# NANO33BLE.net
KiCad netlist of a schematic drawn in Altium Designer
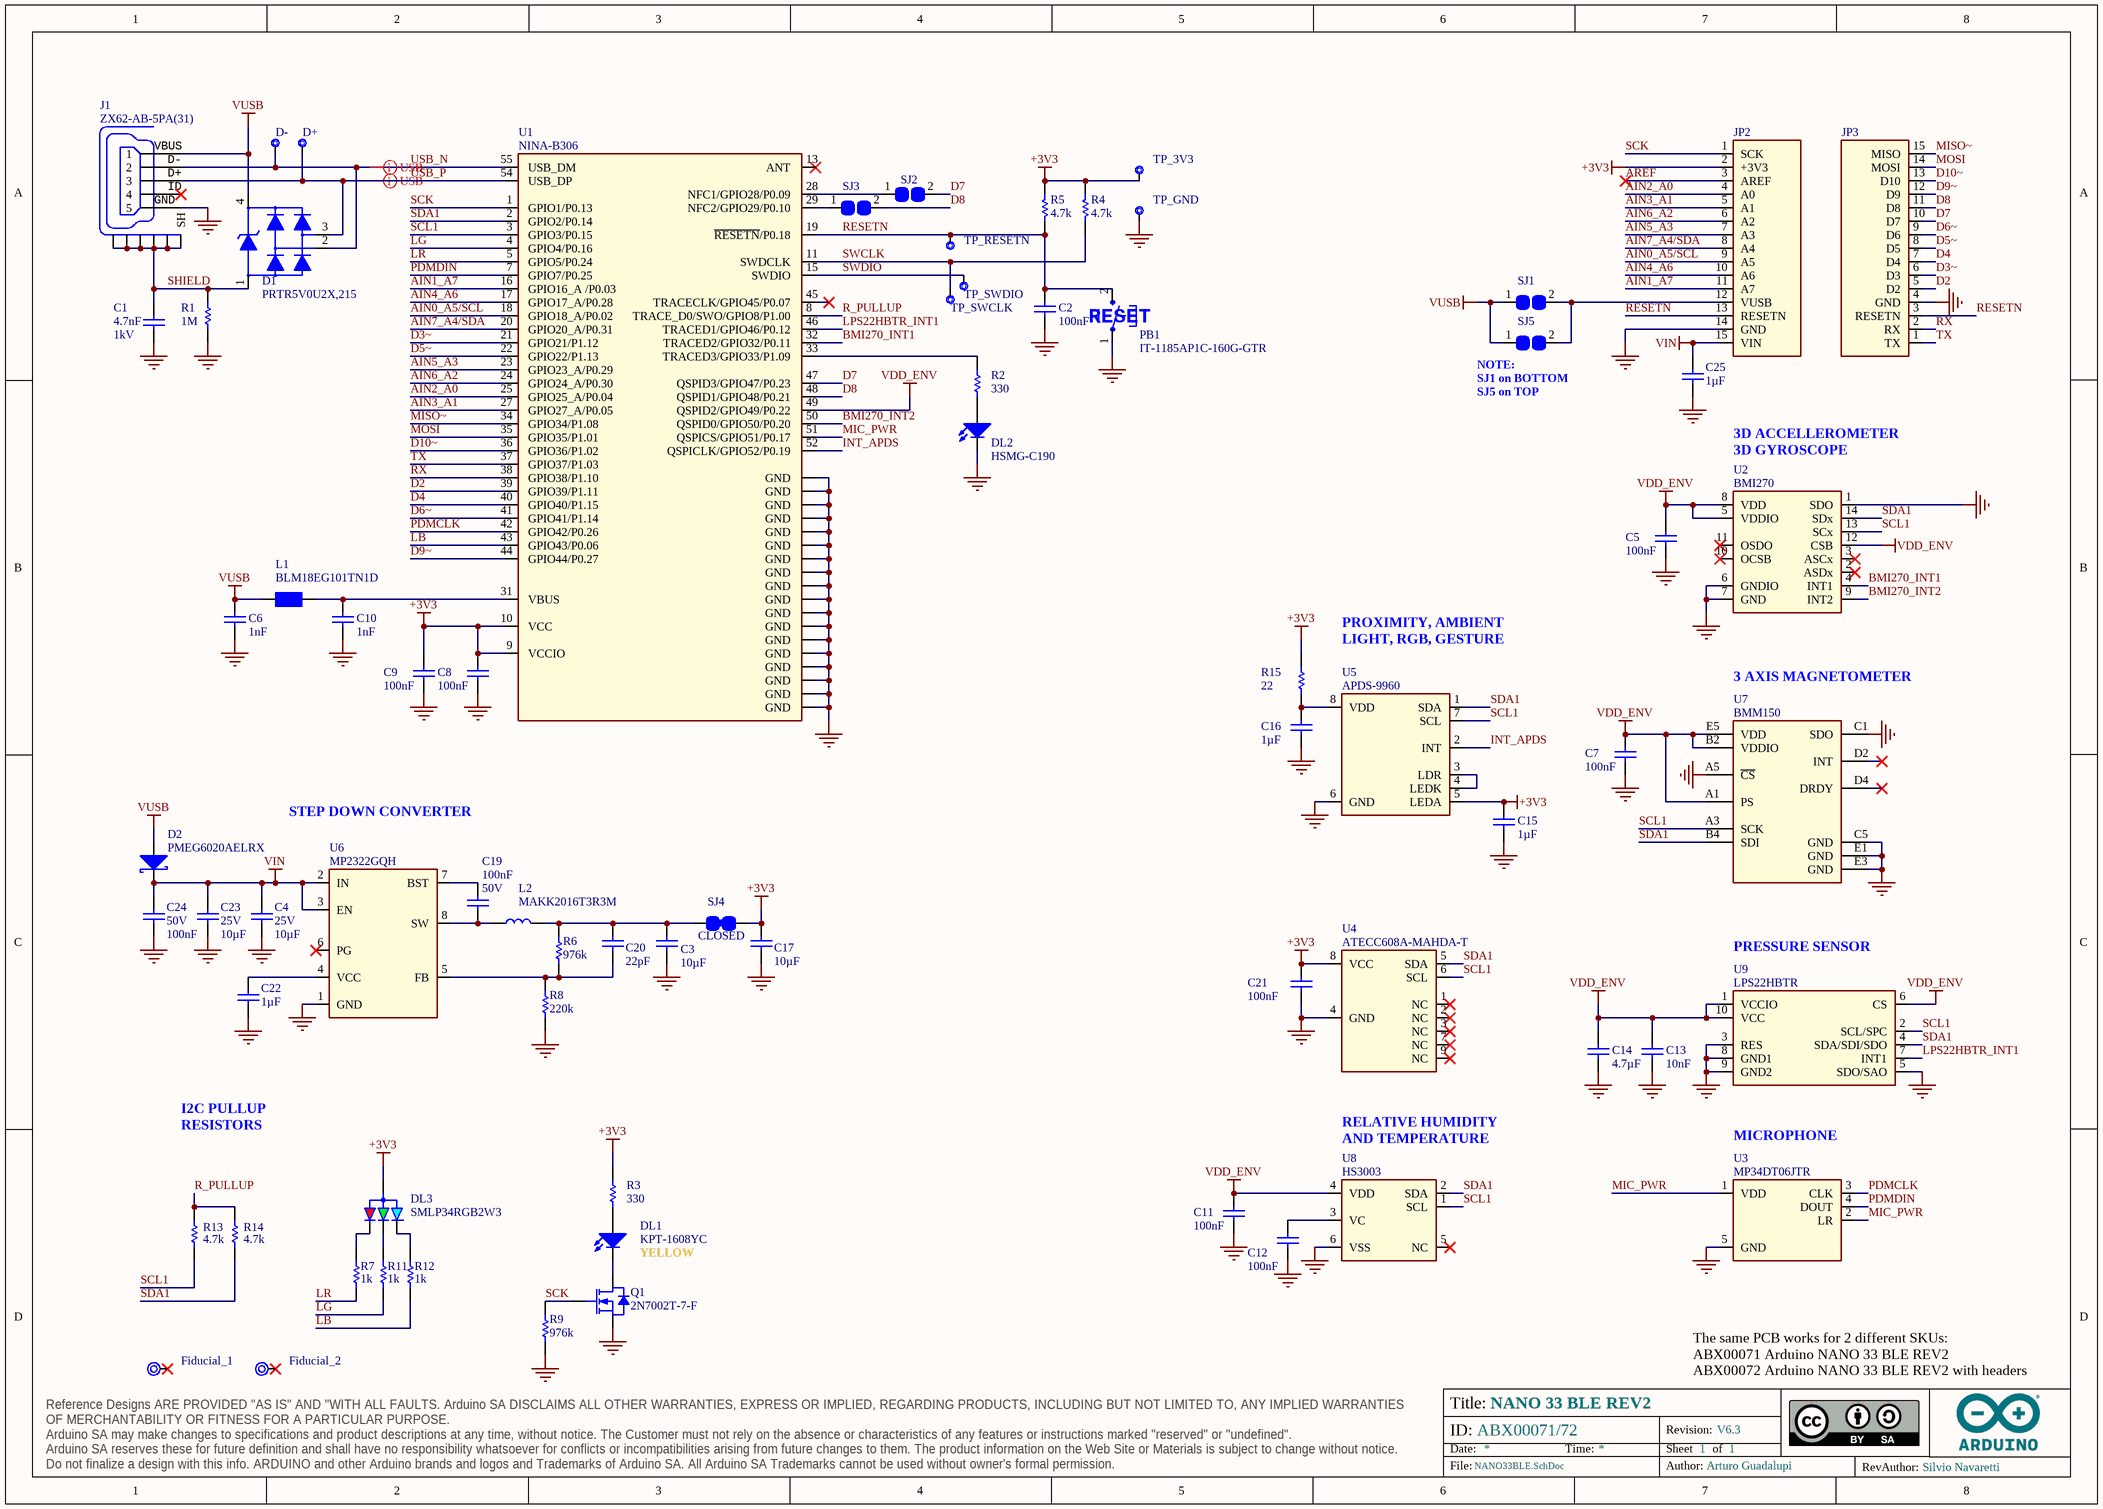
[diagram p0: NANO33BLE.SchDoc]

(export (version "E")
  (design (tool "Eeschema 10.0.6"))
  (components
    (comp (ref "C1")
      (value "4.7nF")
      (footprint "CAP-0805")
      (description "CAP CHIP 0805 4.7nF 10% 1000V X7R")
      (fields
        (field (name "MANUFACTURER") "PSA Shenzen")
        (field (name "VOLTAGE") "1kV")
        (field (name "TOLERANCE") "10%")
      )
      (libsource (lib "Clean") (part "CAP"))
    )
    (comp (ref "C2")
      (value "100nF")
      (footprint "CAP-0402")
      (description "CAP CHIP 0402 100nF 10% 50V X5R")
      (fields (field (name "MANUFACTURER") "Murata") (field (name "PART NUMBER") "GRM155R61H104KE19D"))
      (libsource (lib "Clean") (part "CAP"))
    )
    (comp (ref "C3")
      (value "10µF")
      (footprint "CAP-0603")
      (description "CAP CHIP 0603 10uF 20% 25V X5R")
      (fields (field (name "VOLTAGE") "25V") (field (name "PART NUMBER") "C1608A106M250NT"))
      (libsource (lib "Clean") (part "CAP"))
    )
    (comp (ref "C4")
      (value "10µF")
      (footprint "CAP-0603")
      (description "CAP CHIP 0603 10uF 20% 25V X5R")
      (fields
        (field (name "VOLTAGE") "25V")
        (field (name "PART NUMBER") "C1608A106M250NT")
        (field (name "TOLERANCE") "20%")
      )
      (libsource (lib "Clean") (part "CAP"))
    )
    (comp (ref "C5")
      (value "100nF")
      (footprint "CAP-0402")
      (description "CAP CHIP 0402 100nF 10% 16V X7R")
      (fields (field (name "MANUFACTURER") "Walsin") (field (name "PART NUMBER") "0402B104K160CT"))
      (libsource (lib "Clean") (part "CAP"))
    )
    (comp (ref "C6")
      (value "1nF")
      (footprint "CAP-0402")
      (description "CAP CHIP 0402 1nF 10% 50V X7R")
      (fields (field (name "MANUFACTURER") "KEMET") (field (name "PART NUMBER") "GRM155R71H102KA01D"))
      (libsource (lib "Clean") (part "CAP"))
    )
    (comp (ref "C7")
      (value "100nF")
      (footprint "CAP-0402")
      (description "CAP CHIP 0402 100nF 10% 50V X5R")
      (fields (field (name "VOLTAGE") "50V") (field (name "TOLERANCE") "10%"))
      (libsource (lib "Clean") (part "CAP"))
    )
    (comp (ref "C8")
      (value "100nF")
      (footprint "CAP-0402")
      (description "CAP CHIP 0402 100nF 10% 50V X5R")
      (fields (field (name "MANUFACTURER") "Murata") (field (name "PART NUMBER") "GRM155R61H104KE19D"))
      (libsource (lib "Clean") (part "CAP"))
    )
    (comp (ref "C9")
      (value "100nF")
      (footprint "CAP-0402")
      (description "CAP CHIP 0402 100nF 10% 50V X5R")
      (fields (field (name "MANUFACTURER") "Murata") (field (name "PART NUMBER") "GRM155R61H104KE19D"))
      (libsource (lib "Clean") (part "CAP"))
    )
    (comp (ref "C10")
      (value "1nF")
      (footprint "CAP-0402")
      (description "CAP CHIP 0402 1nF 10% 50V X7R")
      (fields (field (name "MANUFACTURER") "KEMET") (field (name "PART NUMBER") "GRM155R71H102KA01D"))
      (libsource (lib "Clean") (part "CAP"))
    )
    (comp (ref "C11")
      (value "100nF")
      (footprint "CAP-0402")
      (description "CAP CHIP 0402 100nF 10% 50V X5R")
      (fields (field (name "MANUFACTURER") "Murata") (field (name "PART NUMBER") "GRM155R61H104KE19D"))
      (libsource (lib "Clean") (part "CAP"))
    )
    (comp (ref "C12")
      (value "100nF")
      (footprint "CAP-0402")
      (description "CAP CHIP 0402 100nF 10% 50V X5R")
      (fields (field (name "MANUFACTURER") "Murata") (field (name "PART NUMBER") "GRM155R61H104KE19D"))
      (libsource (lib "Clean") (part "CAP"))
    )
    (comp (ref "C13")
      (value "10nF")
      (footprint "CAP-0402")
      (description "CAP CHIP 0402 10nF 10% 50V X7R")
      (fields (field (name "MANUFACTURER") "Hottech") (field (name "VOLTAGE") "50V"))
      (libsource (lib "Clean") (part "CAP"))
    )
    (comp (ref "C14")
      (value "4.7µF")
      (footprint "CAP-0402")
      (description "CAP CHIP 0402 4.7uF 20% 6V3 X5R")
      (fields (field (name "MANUFACTURER") "Hottech") (field (name "PART NUMBER") "C1005A475M6R3NT"))
      (libsource (lib "Clean") (part "CAP"))
    )
    (comp (ref "C15")
      (value "1µF")
      (footprint "CAP-0402")
      (description "CAP CHIP 0402 1uF 10% 10V X5R")
      (fields (field (name "MANUFACTURER") "Samsung Electro-Mechanics") (field (name "VOLTAGE") "10V"))
      (libsource (lib "Clean") (part "CAP"))
    )
    (comp (ref "C16")
      (value "1µF")
      (footprint "CAP-0402")
      (description "CAP CHIP 0402 1uF 10% 10V X5R")
      (fields (field (name "MANUFACTURER") "Samsung Electro-Mechanics") (field (name "VOLTAGE") "10V"))
      (libsource (lib "Clean") (part "CAP"))
    )
    (comp (ref "C17")
      (value "10µF")
      (footprint "CAP-0603")
      (description "CAP CHIP 0603 10uF 20% 25V X5R")
      (fields (field (name "VOLTAGE") "25V") (field (name "PART NUMBER") "C1608A106M250NT"))
      (libsource (lib "Clean") (part "CAP"))
    )
    (comp (ref "C19")
      (value "100nF")
      (footprint "CAP-0402")
      (description "CAP CHIP 0402 100nF 10% 50V X5R")
      (fields
        (field (name "VOLTAGE") "50V")
        (field (name "PART NUMBER") "GRM155R61H104KE19D")
        (field (name "MANUFACTURER") "Murata")
      )
      (libsource (lib "Clean") (part "CAP"))
    )
    (comp (ref "C20")
      (value "22pF")
      (footprint "CAP-0402")
      (description "CAP CHIP 0402 22pF 5% 50V C0G")
      (fields (field (name "TOLERANCE") "5%") (field (name "PART NUMBER") "0402N220J500CT"))
      (libsource (lib "Clean") (part "CAP"))
    )
    (comp (ref "C21")
      (value "100nF")
      (footprint "CAP-0402")
      (description "CAP CHIP 0402 100nF 10% 50V X5R")
      (fields (field (name "MANUFACTURER") "Murata") (field (name "PART NUMBER") "GRM155R61H104KE19D"))
      (libsource (lib "Clean") (part "CAP"))
    )
    (comp (ref "C22")
      (value "1µF")
      (footprint "CAP-0402")
      (description "CAP CHIP 0402 1uF 10% 10V X5R")
      (fields (field (name "TOLERANCE") "10%") (field (name "MANUFACTURER") "Samsung Electro-Mechanics"))
      (libsource (lib "Clean") (part "CAP"))
    )
    (comp (ref "C23")
      (value "10µF")
      (footprint "CAP-0603")
      (description "CAP CHIP 0603 10uF 20% 25V X5R")
      (fields
        (field (name "VOLTAGE") "25V")
        (field (name "PART NUMBER") "C1608A106M250NT")
        (field (name "TOLERANCE") "20%")
      )
      (libsource (lib "Clean") (part "CAP"))
    )
    (comp (ref "C24")
      (value "100nF")
      (footprint "CAP-0402")
      (description "CAP CHIP 0402 100nF 10% 50V X5R")
      (fields
        (field (name "MANUFACTURER") "Murata")
        (field (name "PART NUMBER") "GRM155R61H104KE19D")
        (field (name "VOLTAGE") "50V")
      )
      (libsource (lib "Clean") (part "CAP"))
    )
    (comp (ref "C25")
      (value "1µF")
      (footprint "CAP-0402")
      (description "CAP CHIP 0402 1uF 10% 10V X5R")
      (fields
        (field (name "MANUFACTURER") "Samsung Electro-Mechanics")
        (field (name "PART NUMBER") "CL05A105KP5NNNC")
      )
      (libsource (lib "Clean") (part "CAP"))
    )
    (comp (ref "D+")
      (value "CMP-018-0005-A.3")
      (footprint "TP-1.00MM")
      (description "Test point 1.00mm")
      (libsource (lib "Clean") (part "TESTPOINT"))
    )
    (comp (ref "D-")
      (value "CMP-018-0005-A.3")
      (footprint "TP-1.00MM")
      (description "Test point 1.00mm")
      (libsource (lib "Clean") (part "TESTPOINT"))
    )
    (comp (ref "D1")
      (value "PRTR5V0U2X,215")
      (footprint "SOT190P230X110-4N")
      (description "TVS ARRAY 4LIN.8kV 1pF SOT143B")
      (fields (field (name "MANUFACTURER") "Nexperia"))
      (libsource (lib "Clean") (part "PRTR5V0U2X,215"))
    )
    (comp (ref "D2")
      (value "PMEG6020AELRX")
      (footprint "SOD123-1")
      (description "DIODE SCHOTTKY SMD 2A 60V SOD123FL")
      (fields (field (name "MANUFACTURER") "Nexperia"))
      (libsource (lib "Clean") (part "PMEG6020AELRX"))
    )
    (comp (ref "DL1")
      (value "KPT-1608YC")
      (footprint "LEDC1608X80N-AK")
      (description "LED SMD 0603 GIA588   8mcd 120^")
      (fields (field (name "MANUFACTURER") "Kingbright"))
      (libsource (lib "Clean") (part "LED"))
    )
    (comp (ref "DL2")
      (value "HSMG-C190")
      (footprint "LEDC1608X80N-AK")
      (description "LED SMD 0603 GREEN/568 15mcd 120^")
      (fields (field (name "MANUFACTURER") "Broadcom"))
      (libsource (lib "Clean") (part "LED"))
    )
    (comp (ref "DL3")
      (value "SMLP34RGB2W3")
      (footprint "SMLP34RGB2W")
      (description "LED RGB DIFFUSED PICOLED SMD")
      (fields (field (name "MANUFACTURER") "ROHM Semiconductor"))
      (libsource (lib "Clean") (part "SMLP34RGB2W3"))
    )
    (comp (ref "Fiducial_1")
      (value "Fiducial mark 1mm with 2mm solder")
      (footprint "Fiducial mark 1mm with circle-Footprint-1")
      (libsource (lib "Clean") (part "Fiducial mark 1mm with circle"))
    )
    (comp (ref "Fiducial_2")
      (value "Fiducial mark 1mm with 2mm solder")
      (footprint "Fiducial mark 1mm with circle-Footprint-1")
      (libsource (lib "Clean") (part "Fiducial mark 1mm with circle"))
    )
    (comp (ref "J1")
      (value "ZX62-AB-5PA(31)")
      (footprint "ZX62-AB-5PA")
      (description "CONN USB MICRO F/90^ SMD TipoAB 5x1")
      (fields (field (name "MANUFACTURER") "Hirose"))
      (libsource (lib "Clean") (part "ZX62-AB-5PA(31)"))
    )
    (comp (ref "JP2")
      (value "PINHD-1X15-NANO-ANALOG-CASTELLATED")
      (footprint "PINHD-1X14_5VF")
      (description "CONN THD SOCKET F/1/D 15V JANALOG NANO-TYPE CASTELLATED")
      (libsource (lib "Clean") (part "PINHD-1X15-NANO-ANALOG-CASTELLATED"))
    )
    (comp (ref "JP3")
      (value "PINHD-1X15-NANO-DIGITAL-CASTELLATED")
      (footprint "PINHD-1X14_5VF")
      (description "CONN THD SOCKET F/1/D 15V JDIGITAL NANO-TYPE CASTELLATED")
      (libsource (lib "Clean") (part "PINHD-1X15-NANO-DIGITAL"))
    )
    (comp (ref "L1")
      (value "BLM18EG101TN1D")
      (footprint "L-0603")
      (description "FERRITE SMD 0603 45mOHM 2A")
      (fields
        (field (name "MANUFACTURER") "Murata")
        (field (name "PART NUMBER") "BLM18EG101TN1D")
        (field (name "TOLERANCE") "25%")
      )
      (libsource (lib "Clean") (part "Ferrite"))
    )
    (comp (ref "L2")
      (value "MAKK2016T3R3M")
      (footprint "MAKK2016T3R3M-Footprint-1")
      (description "IND CHIP 0806 3.3 uH 20% 1.2A")
      (fields (field (name "TOLERANCE") "20%") (field (name "MANUFACTURER") "Taiyo Yuden"))
      (libsource (lib "Clean") (part "Inductor"))
    )
    (comp (ref "PB1")
      (value "IT-1185AP1C-160G-GTR")
      (footprint "C&K_PTS820_NO_HOLES-1")
      (description "PUSHBUTTON WHITE NO ANCHORS")
      (fields (field (name "MANUFACTURER") "Switronic"))
      (libsource (lib "Clean") (part "PTS820"))
    )
    (comp (ref "Q1")
      (value "2N7002T-7-F")
      (footprint "SOT523")
      (description "MOSFET N-CH 60V 115mA SOT523")
      (fields (field (name "MANUFACTURER") "Diodes Inc."))
      (libsource (lib "Clean") (part "NMOS"))
    )
    (comp (ref "R1")
      (value "1M")
      (footprint "RES-0402")
      (description "RES CHIP 0402 1M 1% 1/16W")
      (fields (field (name "MANUFACTURER") "Vishay") (field (name "POWER") "62.5mW"))
      (libsource (lib "Clean") (part "RES"))
    )
    (comp (ref "R2")
      (value "330")
      (footprint "RES-0402")
      (description "RES CHIP 0402 330R 5% 1/16W")
      (fields (field (name "MANUFACTURER") "Vishay") (field (name "POWER") "62.5mW"))
      (libsource (lib "Clean") (part "RES"))
    )
    (comp (ref "R3")
      (value "330")
      (footprint "RES-0402")
      (description "RES CHIP 0402 330R 5% 1/16W")
      (fields (field (name "MANUFACTURER") "Vishay") (field (name "POWER") "62.5mW"))
      (libsource (lib "Clean") (part "RES"))
    )
    (comp (ref "R4")
      (value "4.7k")
      (footprint "RES-0402")
      (description "RES CHIP 0402 4k7 1% 1/16W")
      (fields (field (name "MANUFACTURER") "YAGEO") (field (name "PART NUMBER") "RC0402FR-074K7L"))
      (libsource (lib "Clean") (part "RES"))
    )
    (comp (ref "R5")
      (value "4.7k")
      (footprint "RES-0402")
      (description "RES CHIP 0402 4k7 1% 1/16W")
      (fields (field (name "MANUFACTURER") "YAGEO") (field (name "PART NUMBER") "RC0402FR-074K7L"))
      (libsource (lib "Clean") (part "RES"))
    )
    (comp (ref "R6")
      (value "976k")
      (footprint "RES-0402")
      (description "RES CHIP 0402 976k 1% 1/16W")
      (fields (field (name "TOLERANCE") "1%") (field (name "POWER") "62.5mW"))
      (libsource (lib "Clean") (part "RES"))
    )
    (comp (ref "R7")
      (value "1k")
      (footprint "RES-0402")
      (description "RES CHIP 0402 1k 1% 1/16W")
      (fields (field (name "MANUFACTURER") "Vishay") (field (name "POWER") "62.5mW"))
      (libsource (lib "Clean") (part "RES"))
    )
    (comp (ref "R8")
      (value "220k")
      (footprint "RES-0402")
      (description "RES CHIP 0402 220k 1% 1/16W")
      (fields (field (name "MANUFACTURER") "Vishay") (field (name "PART NUMBER") "CRCW0402220KFKED"))
      (libsource (lib "Clean") (part "RES"))
    )
    (comp (ref "R9")
      (value "976k")
      (footprint "RES-0402")
      (description "RES CHIP 0402 976k 1% 1/16W")
      (fields (field (name "TOLERANCE") "1%") (field (name "POWER") "62.5mW"))
      (libsource (lib "Clean") (part "RES"))
    )
    (comp (ref "R11")
      (value "1k")
      (footprint "RES-0402")
      (description "RES CHIP 0402 1k 1% 1/16W")
      (fields (field (name "MANUFACTURER") "Vishay") (field (name "POWER") "62.5mW"))
      (libsource (lib "Clean") (part "RES"))
    )
    (comp (ref "R12")
      (value "1k")
      (footprint "RES-0402")
      (description "RES CHIP 0402 1k 1% 1/16W")
      (fields (field (name "MANUFACTURER") "Vishay") (field (name "POWER") "62.5mW"))
      (libsource (lib "Clean") (part "RES"))
    )
    (comp (ref "R13")
      (value "4.7k")
      (footprint "RES-0402")
      (description "RES CHIP 0402 4k7 1% 1/16W")
      (fields (field (name "MANUFACTURER") "YAGEO") (field (name "PART NUMBER") "RC0402FR-074K7L"))
      (libsource (lib "Clean") (part "RES"))
    )
    (comp (ref "R14")
      (value "4.7k")
      (footprint "RES-0402")
      (description "RES CHIP 0402 4k7 1% 1/16W")
      (fields (field (name "MANUFACTURER") "YAGEO") (field (name "PART NUMBER") "RC0402FR-074K7L"))
      (libsource (lib "Clean") (part "RES"))
    )
    (comp (ref "R15")
      (value "22")
      (footprint "RES-0402")
      (description "RES CHIP 0402 22R 1% 1/16W")
      (fields (field (name "MANUFACTURER") "YAGEO") (field (name "TOLERANCE") "1%"))
      (libsource (lib "Clean") (part "RES"))
    )
    (comp (ref "SJ1")
      (value "SMD solder JUMPER 0805")
      (footprint "SJ")
      (description "Solder Jumper 0805 THIS IS NOT A COMPONENT")
      (libsource (lib "Clean") (part "SJ"))
    )
    (comp (ref "SJ2")
      (value "SMD solder JUMPER 0805")
      (footprint "SJ")
      (description "Solder Jumper 0805 THIS IS NOT A COMPONENT")
      (libsource (lib "Clean") (part "SJ"))
    )
    (comp (ref "SJ3")
      (value "SMD solder JUMPER 0805")
      (footprint "SJ")
      (description "Solder Jumper 0805 THIS IS NOT A COMPONENT")
      (libsource (lib "Clean") (part "SJ"))
    )
    (comp (ref "SJ4")
      (value "SMD solder JUMPER CLOSED")
      (footprint "SJ")
      (description "Solder Jumper shorted pads. This is not a component")
      (libsource (lib "Clean") (part "CLOSED"))
    )
    (comp (ref "SJ5")
      (value "SMD solder JUMPER 0805")
      (footprint "SJ")
      (description "Solder Jumper 0805 THIS IS NOT A COMPONENT")
      (libsource (lib "Clean") (part "SJ"))
    )
    (comp (ref "TP_3V3")
      (value "CMP-018-0005-A.3")
      (footprint "TP-1.00MM")
      (description "Test point 1.00mm")
      (libsource (lib "Clean") (part "TESTPOINT"))
    )
    (comp (ref "TP_GND")
      (value "CMP-018-0005-A.3")
      (footprint "TP-1.00MM")
      (description "Test point 1.00mm")
      (libsource (lib "Clean") (part "TESTPOINT"))
    )
    (comp (ref "TP_RESETN")
      (value "CMP-018-0005-A.3")
      (footprint "TP-1.00MM")
      (description "Test point 1.00mm")
      (libsource (lib "Clean") (part "TESTPOINT"))
    )
    (comp (ref "TP_SWCLK")
      (value "CMP-018-0005-A.3")
      (footprint "TP-1.00MM")
      (description "Test point 1.00mm")
      (libsource (lib "Clean") (part "TESTPOINT"))
    )
    (comp (ref "TP_SWDIO")
      (value "CMP-018-0005-A.3")
      (footprint "TP-1.00MM")
      (description "Test point 1.00mm")
      (libsource (lib "Clean") (part "TESTPOINT"))
    )
    (comp (ref "U1")
      (value "NINA-B306")
      (footprint "NINA-B3X")
      (description "MODULE BLE 5.0 STAND ALONE nRF52")
      (fields (field (name "MANUFACTURER") "UBlox"))
      (libsource (lib "Clean") (part "NINA-B306-Symbol-1"))
    )
    (comp (ref "U2")
      (value "BMI270")
      (footprint "VFLGA14")
      (description "IC IMU 6 AXIS 14VFLGA pin to pin alternative to LSM6DSOXTR")
      (fields (field (name "MANUFACTURER") "Bosch Sensortec"))
      (libsource (lib "Clean") (part "BMI270-Symbol-1"))
    )
    (comp (ref "U3")
      (value "MP34DT06JTR")
      (footprint "HCLGA")
      (description "SENS MEMS AUDIO OMNIDIRECTIONAL")
      (fields (field (name "MANUFACTURER") "ST Microelectronics"))
      (libsource (lib "Clean") (part "MP34DT06JTR"))
    )
    (comp (ref "U4")
      (value "ATECC608A-MAHDA-T")
      (footprint "UDFN8")
      (description "IC AUTHENTICATION CHIP UDFN8")
      (fields (field (name "MANUFACTURER") "Microchip"))
      (libsource (lib "Clean") (part "ATECC608A-MAHDA-T"))
    )
    (comp (ref "U5")
      (value "APDS-9960")
      (footprint "APDS-9660-Footprint-1")
      (description "IC SENS OPT 560NM AMBIENT MODULE APDS-9960")
      (fields (field (name "MANUFACTURER") "Broadcom"))
      (libsource (lib "Clean") (part "APDS-9660"))
    )
    (comp (ref "U6")
      (value "MP2322GQH")
      (footprint "QFN50P150X200X90-8L")
      (description "IC STEP DOWN CONV 1A 22V QFN8")
      (fields (field (name "MANUFACTURER") "Monolithic Power Systems"))
      (libsource (lib "Clean") (part "MP2322GQH"))
    )
    (comp (ref "U7")
      (value "BMM150")
      (footprint "FP-BMM150-MFG")
      (description "IC SENSOR 3-AXIS GEOMAGNETIC")
      (fields (field (name "MANUFACTURER") "Bosch Sensortec"))
      (libsource (lib "Clean") (part "24d48050165bead51c97f0d4a59b4f7"))
    )
    (comp (ref "U8")
      (value "HS3003")
      (footprint "HS3003-Footprint-1")
      (description "IC PRESSURE AND TEMPERATURE SENSOR 6-LGA")
      (fields (field (name "MANUFACTURER") "Renesas"))
      (libsource (lib "Clean") (part "HS3003-Symbol-1"))
    )
    (comp (ref "U9")
      (value "LPS22HBTR")
      (footprint "LPS22H")
      (description "SENSOR PRESSURE 3.77 PSI ~ 18.27 PSI (26 kPa ~ 126 kPa) Absolute 24 b 10-WFLGA")
      (fields (field (name "MANUFACTURER") "ST Microelectronics"))
      (libsource (lib "Clean") (part "LPS22HBTR"))
    )
  )
  (nets
    (net (code "1") (name "+3V3") (class "Default")
      (node (ref "C15") (pin "2") (pinfunction "2_2") (pintype "passive"))
      (node (ref "C17") (pin "2") (pinfunction "2_2") (pintype "passive"))
      (node (ref "C21") (pin "2") (pinfunction "2_2") (pintype "passive"))
      (node (ref "C8") (pin "2") (pinfunction "2_2") (pintype "passive"))
      (node (ref "C9") (pin "1") (pinfunction "1_1") (pintype "passive"))
      (node (ref "DL3") (pin "1") (pinfunction "ANODE_1") (pintype "passive"))
      (node (ref "JP2") (pin "2") (pinfunction "+3V3_2") (pintype "passive"))
      (node (ref "R15") (pin "2") (pinfunction "2_2") (pintype "passive"))
      (node (ref "R3") (pin "2") (pinfunction "2_2") (pintype "passive"))
      (node (ref "R4") (pin "2") (pinfunction "2_2") (pintype "passive"))
      (node (ref "R5") (pin "2") (pinfunction "2_2") (pintype "passive"))
      (node (ref "SJ4") (pin "2") (pinfunction "2_2") (pintype "passive"))
      (node (ref "TP_3V3") (pin "X") (pinfunction "X_X") (pintype "passive"))
      (node (ref "U1") (pin "10") (pinfunction "VCC_10") (pintype "power_in"))
      (node (ref "U1") (pin "9") (pinfunction "VCCIO_9") (pintype "power_in"))
      (node (ref "U4") (pin "8") (pinfunction "VCC_8") (pintype "passive"))
      (node (ref "U5") (pin "5") (pinfunction "LEDA_5") (pintype "passive"))
    )
    (net (code "2") (name "/AIN0_A5{slash}SCL") (class "Default")
      (node (ref "JP2") (pin "9") (pinfunction "A5_9") (pintype "passive"))
      (node (ref "U1") (pin "18") (pinfunction "GPIO18_A/P0.02_18") (pintype "passive"))
    )
    (net (code "3") (name "/AIN1_A7") (class "Default")
      (node (ref "JP2") (pin "11") (pinfunction "A7_11") (pintype "passive"))
      (node (ref "U1") (pin "16") (pinfunction "GPIO16_A_/P0.03_16") (pintype "passive"))
    )
    (net (code "4") (name "/AIN2_A0") (class "Default")
      (node (ref "JP2") (pin "4") (pinfunction "A0_4") (pintype "passive"))
      (node (ref "U1") (pin "25") (pinfunction "GPIO25_A/P0.04_25") (pintype "passive"))
    )
    (net (code "5") (name "/AIN3_A1") (class "Default")
      (node (ref "JP2") (pin "5") (pinfunction "A1_5") (pintype "passive"))
      (node (ref "U1") (pin "27") (pinfunction "GPIO27_A/P0.05_27") (pintype "passive"))
    )
    (net (code "6") (name "/AIN4_A6") (class "Default")
      (node (ref "JP2") (pin "10") (pinfunction "A6_10") (pintype "passive"))
      (node (ref "U1") (pin "17") (pinfunction "GPIO17_A/P0.28_17") (pintype "passive"))
    )
    (net (code "7") (name "/AIN5_A3") (class "Default")
      (node (ref "JP2") (pin "7") (pinfunction "A3_7") (pintype "passive"))
      (node (ref "U1") (pin "23") (pinfunction "GPIO23_A/P0.29_23") (pintype "passive"))
    )
    (net (code "8") (name "/AIN6_A2") (class "Default")
      (node (ref "JP2") (pin "6") (pinfunction "A2_6") (pintype "passive"))
      (node (ref "U1") (pin "24") (pinfunction "GPIO24_A/P0.30_24") (pintype "passive"))
    )
    (net (code "9") (name "/AIN7_A4{slash}SDA") (class "Default")
      (node (ref "JP2") (pin "8") (pinfunction "A4_8") (pintype "passive"))
      (node (ref "U1") (pin "20") (pinfunction "GPIO20_A/P0.31_20") (pintype "passive"))
    )
    (net (code "10") (name "/AREF") (class "Default")
      (node (ref "JP2") (pin "3") (pinfunction "AREF_3") (pintype "passive+no_connect"))
    )
    (net (code "11") (name "/BMI270_INT1") (class "Default")
      (node (ref "U1") (pin "32") (pinfunction "TRACED2/GPIO32/P0.11_32") (pintype "passive"))
      (node (ref "U2") (pin "4") (pinfunction "INT1_4") (pintype "passive"))
    )
    (net (code "12") (name "/BMI270_INT2") (class "Default")
      (node (ref "U1") (pin "50") (pinfunction "QSPID0/GPIO50/P0.20_50") (pintype "passive"))
      (node (ref "U2") (pin "9") (pinfunction "INT2_9") (pintype "passive"))
    )
    (net (code "13") (name "/D2") (class "Default")
      (node (ref "JP3") (pin "5") (pinfunction "D2_5") (pintype "passive"))
      (node (ref "U1") (pin "39") (pinfunction "GPIO39/P1.11_39") (pintype "passive"))
    )
    (net (code "14") (name "/D3~") (class "Default")
      (node (ref "JP3") (pin "6") (pinfunction "D3_6") (pintype "passive"))
      (node (ref "U1") (pin "21") (pinfunction "GPIO21/P1.12_21") (pintype "passive"))
    )
    (net (code "15") (name "/D4") (class "Default")
      (node (ref "JP3") (pin "7") (pinfunction "D4_7") (pintype "passive"))
      (node (ref "U1") (pin "40") (pinfunction "GPIO40/P1.15_40") (pintype "passive"))
    )
    (net (code "16") (name "/D5~") (class "Default")
      (node (ref "JP3") (pin "8") (pinfunction "D5_8") (pintype "passive"))
      (node (ref "U1") (pin "22") (pinfunction "GPIO22/P1.13_22") (pintype "passive"))
    )
    (net (code "17") (name "/D6~") (class "Default")
      (node (ref "JP3") (pin "9") (pinfunction "D6_9") (pintype "passive"))
      (node (ref "U1") (pin "41") (pinfunction "GPIO41/P1.14_41") (pintype "passive"))
    )
    (net (code "18") (name "/D7") (class "Default")
      (node (ref "JP3") (pin "10") (pinfunction "D7_10") (pintype "passive"))
      (node (ref "SJ2") (pin "2") (pinfunction "2_2") (pintype "passive"))
      (node (ref "U1") (pin "47") (pinfunction "QSPID3/GPIO47/P0.23_47") (pintype "passive"))
    )
    (net (code "19") (name "/D8") (class "Default")
      (node (ref "JP3") (pin "11") (pinfunction "D8_11") (pintype "passive"))
      (node (ref "SJ3") (pin "2") (pinfunction "2_2") (pintype "passive"))
      (node (ref "U1") (pin "48") (pinfunction "QSPID1/GPIO48/P0.21_48") (pintype "passive"))
    )
    (net (code "20") (name "/D9~") (class "Default")
      (node (ref "JP3") (pin "12") (pinfunction "D9_12") (pintype "passive"))
      (node (ref "U1") (pin "44") (pinfunction "GPIO44/P0.27_44") (pintype "passive"))
    )
    (net (code "21") (name "/D10~") (class "Default")
      (node (ref "JP3") (pin "13") (pinfunction "D10_13") (pintype "passive"))
      (node (ref "U1") (pin "36") (pinfunction "GPIO36/P1.02_36") (pintype "passive"))
    )
    (net (code "22") (name "/INT_APDS") (class "Default")
      (node (ref "U1") (pin "52") (pinfunction "QSPICLK/GPIO52/P0.19_52") (pintype "passive"))
      (node (ref "U5") (pin "2") (pinfunction "INT_2") (pintype "passive"))
    )
    (net (code "23") (name "/LB") (class "Default")
      (node (ref "R12") (pin "1") (pinfunction "1_1") (pintype "passive"))
      (node (ref "U1") (pin "43") (pinfunction "GPIO43/P0.06_43") (pintype "passive"))
    )
    (net (code "24") (name "/LG") (class "Default")
      (node (ref "R11") (pin "1") (pinfunction "1_1") (pintype "passive"))
      (node (ref "U1") (pin "4") (pinfunction "GPIO4/P0.16_4") (pintype "passive"))
    )
    (net (code "25") (name "/LPS22HBTR_INT1") (class "Default")
      (node (ref "U1") (pin "46") (pinfunction "TRACED1/GPIO46/P0.12_46") (pintype "passive"))
      (node (ref "U9") (pin "7") (pinfunction "INT1_7") (pintype "passive"))
    )
    (net (code "26") (name "/LR") (class "Default")
      (node (ref "R7") (pin "1") (pinfunction "1_1") (pintype "passive"))
      (node (ref "U1") (pin "5") (pinfunction "GPIO5/P0.24_5") (pintype "passive"))
    )
    (net (code "27") (name "/MIC_PWR") (class "Default")
      (node (ref "U1") (pin "51") (pinfunction "QSPICS/GPIO51/P0.17_51") (pintype "passive"))
      (node (ref "U3") (pin "1") (pinfunction "VDD_1") (pintype "power_in"))
      (node (ref "U3") (pin "2") (pinfunction "LR_2") (pintype "passive"))
    )
    (net (code "28") (name "/MISO~") (class "Default")
      (node (ref "JP3") (pin "15") (pinfunction "MISO_15") (pintype "passive"))
      (node (ref "U1") (pin "34") (pinfunction "GPIO34/P1.08_34") (pintype "passive"))
    )
    (net (code "29") (name "/MOSI") (class "Default")
      (node (ref "JP3") (pin "14") (pinfunction "MOSI_14") (pintype "passive"))
      (node (ref "U1") (pin "35") (pinfunction "GPIO35/P1.01_35") (pintype "passive"))
    )
    (net (code "30") (name "/PDMCLK") (class "Default")
      (node (ref "U1") (pin "42") (pinfunction "GPIO42/P0.26_42") (pintype "passive"))
      (node (ref "U3") (pin "3") (pinfunction "CLK_3") (pintype "passive"))
    )
    (net (code "31") (name "/PDMDIN") (class "Default")
      (node (ref "U1") (pin "7") (pinfunction "GPIO7/P0.25_7") (pintype "passive"))
      (node (ref "U3") (pin "4") (pinfunction "DOUT_4") (pintype "passive"))
    )
    (net (code "32") (name "/RESETN") (class "Default")
      (node (ref "C2") (pin "1") (pinfunction "1_1") (pintype "passive"))
      (node (ref "JP2") (pin "13") (pinfunction "RESETN_13") (pintype "passive"))
      (node (ref "JP3") (pin "3") (pinfunction "RESETN_3") (pintype "passive"))
      (node (ref "PB1") (pin "2") (pinfunction "2_2") (pintype "passive"))
      (node (ref "R5") (pin "1") (pinfunction "1_1") (pintype "passive"))
      (node (ref "TP_RESETN") (pin "X") (pinfunction "X_X") (pintype "passive"))
      (node (ref "U1") (pin "19") (pinfunction "~{RESETN}/P0.18_19") (pintype "passive"))
    )
    (net (code "33") (name "/RX") (class "Default")
      (node (ref "JP3") (pin "2") (pinfunction "RX_2") (pintype "passive"))
      (node (ref "U1") (pin "38") (pinfunction "GPIO38/P1.10_38") (pintype "passive"))
    )
    (net (code "34") (name "/R_PULLUP") (class "Default")
      (node (ref "R13") (pin "2") (pinfunction "2_2") (pintype "passive"))
      (node (ref "R14") (pin "2") (pinfunction "2_2") (pintype "passive"))
      (node (ref "U1") (pin "8") (pinfunction "TRACE_D0/SWO/GPIO8/P1.00_8") (pintype "passive"))
    )
    (net (code "35") (name "/SCK") (class "Default")
      (node (ref "JP2") (pin "1") (pinfunction "SCK_1") (pintype "passive"))
      (node (ref "Q1") (pin "G") (pinfunction "G_G") (pintype "passive"))
      (node (ref "R9") (pin "2") (pinfunction "2_2") (pintype "passive"))
      (node (ref "U1") (pin "1") (pinfunction "GPIO1/P0.13_1") (pintype "passive"))
    )
    (net (code "36") (name "/SCL1") (class "Default")
      (node (ref "R13") (pin "1") (pinfunction "1_1") (pintype "passive"))
      (node (ref "U1") (pin "3") (pinfunction "GPIO3/P0.15_3") (pintype "passive"))
      (node (ref "U2") (pin "13") (pinfunction "SCx_13") (pintype "passive"))
      (node (ref "U4") (pin "6") (pinfunction "SCL_6") (pintype "passive"))
      (node (ref "U5") (pin "7") (pinfunction "SCL_7") (pintype "passive"))
      (node (ref "U7") (pin "A3") (pinfunction "SCK_A3") (pintype "passive"))
      (node (ref "U8") (pin "1") (pinfunction "SCL_1") (pintype "passive"))
      (node (ref "U9") (pin "2") (pinfunction "SCL/SPC_2") (pintype "passive"))
    )
    (net (code "37") (name "/SDA1") (class "Default")
      (node (ref "R14") (pin "1") (pinfunction "1_1") (pintype "passive"))
      (node (ref "U1") (pin "2") (pinfunction "GPIO2/P0.14_2") (pintype "passive"))
      (node (ref "U2") (pin "14") (pinfunction "SDx_14") (pintype "passive"))
      (node (ref "U4") (pin "5") (pinfunction "SDA_5") (pintype "passive"))
      (node (ref "U5") (pin "1") (pinfunction "SDA_1") (pintype "passive"))
      (node (ref "U7") (pin "B4") (pinfunction "SDI_B4") (pintype "passive"))
      (node (ref "U8") (pin "2") (pinfunction "SDA_2") (pintype "passive"))
      (node (ref "U9") (pin "4") (pinfunction "SDA/SDI/SDO_4") (pintype "passive"))
    )
    (net (code "38") (name "/SHIELD") (class "Default")
      (node (ref "C1") (pin "2") (pinfunction "2_2") (pintype "passive"))
      (node (ref "D1") (pin "1") (pinfunction "1_1") (pintype "passive"))
      (node (ref "J1") (pin "M1") (pinfunction "SH_M1") (pintype "passive"))
      (node (ref "J1") (pin "M2") (pinfunction "SH_M2") (pintype "passive"))
      (node (ref "J1") (pin "M3") (pinfunction "SH_M3") (pintype "passive"))
      (node (ref "J1") (pin "M4") (pinfunction "SH_M4") (pintype "passive"))
      (node (ref "J1") (pin "M5") (pinfunction "SH_M5") (pintype "passive"))
      (node (ref "J1") (pin "M6") (pinfunction "SH_M6") (pintype "passive"))
      (node (ref "R1") (pin "2") (pinfunction "2_2") (pintype "passive"))
    )
    (net (code "39") (name "/SWCLK") (class "Default")
      (node (ref "R4") (pin "1") (pinfunction "1_1") (pintype "passive"))
      (node (ref "TP_SWCLK") (pin "X") (pinfunction "X_X") (pintype "passive"))
      (node (ref "U1") (pin "11") (pinfunction "SWDCLK_11") (pintype "passive"))
    )
    (net (code "40") (name "/SWDIO") (class "Default")
      (node (ref "TP_SWDIO") (pin "X") (pinfunction "X_X") (pintype "passive"))
      (node (ref "U1") (pin "15") (pinfunction "SWDIO_15") (pintype "passive"))
    )
    (net (code "41") (name "/TX") (class "Default")
      (node (ref "JP3") (pin "1") (pinfunction "TX_1") (pintype "passive"))
      (node (ref "U1") (pin "37") (pinfunction "GPIO37/P1.03_37") (pintype "passive"))
    )
    (net (code "42") (name "/USB_N") (class "Default")
      (node (ref "D-") (pin "X") (pinfunction "X_X") (pintype "passive"))
      (node (ref "D1") (pin "2") (pinfunction "2_2") (pintype "passive"))
      (node (ref "J1") (pin "2") (pinfunction "2_2") (pintype "passive"))
      (node (ref "U1") (pin "55") (pinfunction "USB_DM_55") (pintype "passive"))
    )
    (net (code "43") (name "/USB_P") (class "Default")
      (node (ref "D+") (pin "X") (pinfunction "X_X") (pintype "passive"))
      (node (ref "D1") (pin "3") (pinfunction "3_3") (pintype "passive"))
      (node (ref "J1") (pin "3") (pinfunction "3_3") (pintype "passive"))
      (node (ref "U1") (pin "54") (pinfunction "USB_DP_54") (pintype "passive"))
    )
    (net (code "44") (name "GND") (class "Default")
      (node (ref "C1") (pin "1") (pinfunction "1_1") (pintype "passive"))
      (node (ref "C10") (pin "2") (pinfunction "2_2") (pintype "passive"))
      (node (ref "C11") (pin "2") (pinfunction "2_2") (pintype "passive"))
      (node (ref "C12") (pin "2") (pinfunction "2_2") (pintype "passive"))
      (node (ref "C13") (pin "2") (pinfunction "2_2") (pintype "passive"))
      (node (ref "C14") (pin "2") (pinfunction "2_2") (pintype "passive"))
      (node (ref "C15") (pin "1") (pinfunction "1_1") (pintype "passive"))
      (node (ref "C16") (pin "1") (pinfunction "1_1") (pintype "passive"))
      (node (ref "C17") (pin "1") (pinfunction "1_1") (pintype "passive"))
      (node (ref "C2") (pin "2") (pinfunction "2_2") (pintype "passive"))
      (node (ref "C21") (pin "1") (pinfunction "1_1") (pintype "passive"))
      (node (ref "C22") (pin "1") (pinfunction "1_1") (pintype "passive"))
      (node (ref "C23") (pin "1") (pinfunction "1_1") (pintype "passive"))
      (node (ref "C24") (pin "2") (pinfunction "2_2") (pintype "passive"))
      (node (ref "C25") (pin "1") (pinfunction "1_1") (pintype "passive"))
      (node (ref "C3") (pin "1") (pinfunction "1_1") (pintype "passive"))
      (node (ref "C4") (pin "1") (pinfunction "1_1") (pintype "passive"))
      (node (ref "C5") (pin "2") (pinfunction "2_2") (pintype "passive"))
      (node (ref "C6") (pin "2") (pinfunction "2_2") (pintype "passive"))
      (node (ref "C7") (pin "1") (pinfunction "1_1") (pintype "passive"))
      (node (ref "C8") (pin "1") (pinfunction "1_1") (pintype "passive"))
      (node (ref "C9") (pin "2") (pinfunction "2_2") (pintype "passive"))
      (node (ref "DL2") (pin "C") (pinfunction "C_C") (pintype "passive"))
      (node (ref "J1") (pin "5") (pinfunction "5_5") (pintype "passive"))
      (node (ref "JP2") (pin "14") (pinfunction "GND_14") (pintype "passive"))
      (node (ref "JP3") (pin "4") (pinfunction "GND_4") (pintype "passive"))
      (node (ref "PB1") (pin "1") (pinfunction "1_1") (pintype "passive"))
      (node (ref "Q1") (pin "S") (pinfunction "S_S") (pintype "passive"))
      (node (ref "R1") (pin "1") (pinfunction "1_1") (pintype "passive"))
      (node (ref "R8") (pin "1") (pinfunction "1_1") (pintype "passive"))
      (node (ref "R9") (pin "1") (pinfunction "1_1") (pintype "passive"))
      (node (ref "TP_GND") (pin "X") (pinfunction "X_X") (pintype "passive"))
      (node (ref "U1") (pin "12") (pinfunction "GND_12") (pintype "power_in"))
      (node (ref "U1") (pin "14") (pinfunction "GND_14") (pintype "power_in"))
      (node (ref "U1") (pin "26") (pinfunction "GND_26") (pintype "power_in"))
      (node (ref "U1") (pin "30") (pinfunction "GND_30") (pintype "power_in"))
      (node (ref "U1") (pin "53") (pinfunction "GND_53") (pintype "power_in"))
      (node (ref "U1") (pin "6") (pinfunction "GND_6") (pintype "power_in"))
      (node (ref "U1") (pin "GND1") (pinfunction "GND_GND1") (pintype "power_in"))
      (node (ref "U1") (pin "GND10") (pinfunction "GND_GND10") (pintype "power_in"))
      (node (ref "U1") (pin "GND11") (pinfunction "GND_GND11") (pintype "power_in"))
      (node (ref "U1") (pin "GND12") (pinfunction "GND_GND12") (pintype "power_in"))
      (node (ref "U1") (pin "GND2") (pinfunction "GND_GND2") (pintype "power_in"))
      (node (ref "U1") (pin "GND3") (pinfunction "GND_GND3") (pintype "power_in"))
      (node (ref "U1") (pin "GND4") (pinfunction "GND_GND4") (pintype "power_in"))
      (node (ref "U1") (pin "GND5") (pinfunction "GND_GND5") (pintype "power_in"))
      (node (ref "U1") (pin "GND6") (pinfunction "GND_GND6") (pintype "power_in"))
      (node (ref "U1") (pin "GND7") (pinfunction "GND_GND7") (pintype "power_in"))
      (node (ref "U1") (pin "GND8") (pinfunction "GND_GND8") (pintype "power_in"))
      (node (ref "U1") (pin "GND9") (pinfunction "GND_GND9") (pintype "power_in"))
      (node (ref "U2") (pin "1") (pinfunction "SDO_1") (pintype "passive"))
      (node (ref "U2") (pin "6") (pinfunction "GNDIO_6") (pintype "passive"))
      (node (ref "U2") (pin "7") (pinfunction "GND_7") (pintype "passive"))
      (node (ref "U3") (pin "5") (pinfunction "GND_5") (pintype "power_in"))
      (node (ref "U4") (pin "4") (pinfunction "GND_4") (pintype "passive"))
      (node (ref "U5") (pin "6") (pinfunction "GND_6") (pintype "power_in"))
      (node (ref "U6") (pin "1") (pinfunction "GND_1") (pintype "passive"))
      (node (ref "U7") (pin "A5") (pinfunction "~{CS}_A5") (pintype "passive"))
      (node (ref "U7") (pin "C1") (pinfunction "SDO_C1") (pintype "passive"))
      (node (ref "U7") (pin "C5") (pinfunction "GND_C5") (pintype "passive"))
      (node (ref "U7") (pin "E1") (pinfunction "GND_E1") (pintype "passive"))
      (node (ref "U7") (pin "E3") (pinfunction "GND_E3") (pintype "passive"))
      (node (ref "U8") (pin "6") (pinfunction "VSS_6") (pintype "passive"))
      (node (ref "U9") (pin "3") (pinfunction "RES_3") (pintype "passive"))
      (node (ref "U9") (pin "5") (pinfunction "SDO/SAO_5") (pintype "passive"))
      (node (ref "U9") (pin "8") (pinfunction "GND1_8") (pintype "passive"))
      (node (ref "U9") (pin "9") (pinfunction "GND2_9") (pintype "passive"))
    )
    (net (code "45") (name "Net-(C20-Pad2)") (class "Default")
      (node (ref "C20") (pin "2") (pinfunction "2_2") (pintype "passive"))
      (node (ref "C3") (pin "2") (pinfunction "2_2") (pintype "passive"))
      (node (ref "L2") (pin "2") (pinfunction "2_2") (pintype "passive"))
      (node (ref "R6") (pin "2") (pinfunction "2_2") (pintype "passive"))
      (node (ref "SJ4") (pin "1") (pinfunction "1_1") (pintype "passive"))
    )
    (net (code "46") (name "Net-(DL1-PadA)") (class "Default")
      (node (ref "DL1") (pin "A") (pinfunction "A_A") (pintype "passive"))
      (node (ref "R3") (pin "1") (pinfunction "1_1") (pintype "passive"))
    )
    (net (code "47") (name "Net-(DL1-PadC)") (class "Default")
      (node (ref "DL1") (pin "C") (pinfunction "C_C") (pintype "passive"))
      (node (ref "Q1") (pin "D") (pinfunction "D_D") (pintype "passive"))
    )
    (net (code "48") (name "Net-(DL2-PadA)") (class "Default")
      (node (ref "DL2") (pin "A") (pinfunction "A_A") (pintype "passive"))
      (node (ref "R2") (pin "1") (pinfunction "1_1") (pintype "passive"))
    )
    (net (code "49") (name "Net-(DL3-BLUE_C)") (class "Default")
      (node (ref "DL3") (pin "3") (pinfunction "BLUE_C_3") (pintype "passive"))
      (node (ref "R12") (pin "2") (pinfunction "2_2") (pintype "passive"))
    )
    (net (code "50") (name "Net-(DL3-GREEN_C)") (class "Default")
      (node (ref "DL3") (pin "4") (pinfunction "GREEN_C_4") (pintype "passive"))
      (node (ref "R11") (pin "2") (pinfunction "2_2") (pintype "passive"))
    )
    (net (code "51") (name "Net-(DL3-RED_C)") (class "Default")
      (node (ref "DL3") (pin "2") (pinfunction "RED_C_2") (pintype "passive"))
      (node (ref "R7") (pin "2") (pinfunction "2_2") (pintype "passive"))
    )
    (net (code "52") (name "Net-(JP2-VUSB)") (class "Default")
      (node (ref "JP2") (pin "12") (pinfunction "VUSB_12") (pintype "passive"))
      (node (ref "SJ1") (pin "2") (pinfunction "2_2") (pintype "passive"))
      (node (ref "SJ5") (pin "2") (pinfunction "2_2") (pintype "passive"))
    )
    (net (code "53") (name "Net-(U1-NFC1{slash}GPIO28{slash}P0.09)") (class "Default")
      (node (ref "SJ2") (pin "1") (pinfunction "1_1") (pintype "passive"))
      (node (ref "U1") (pin "28") (pinfunction "NFC1/GPIO28/P0.09_28") (pintype "passive"))
    )
    (net (code "54") (name "Net-(U1-NFC2{slash}GPIO29{slash}P0.10)") (class "Default")
      (node (ref "SJ3") (pin "1") (pinfunction "1_1") (pintype "passive"))
      (node (ref "U1") (pin "29") (pinfunction "NFC2/GPIO29/P0.10_29") (pintype "passive"))
    )
    (net (code "55") (name "Net-(U1-TRACED3{slash}GPIO33{slash}P1.09)") (class "Default")
      (node (ref "R2") (pin "2") (pinfunction "2_2") (pintype "passive"))
      (node (ref "U1") (pin "33") (pinfunction "TRACED3/GPIO33/P1.09_33") (pintype "passive"))
    )
    (net (code "56") (name "Net-(U1-VBUS)") (class "Default")
      (node (ref "C10") (pin "1") (pinfunction "1_1") (pintype "passive"))
      (node (ref "L1") (pin "2") (pinfunction "2_2") (pintype "passive"))
      (node (ref "U1") (pin "31") (pinfunction "VBUS_31") (pintype "power_in"))
    )
    (net (code "57") (name "Net-(U5-LDR)") (class "Default")
      (node (ref "U5") (pin "3") (pinfunction "LDR_3") (pintype "passive"))
      (node (ref "U5") (pin "4") (pinfunction "LEDK_4") (pintype "passive"))
    )
    (net (code "58") (name "Net-(U5-VDD)") (class "Default")
      (node (ref "C16") (pin "2") (pinfunction "2_2") (pintype "passive"))
      (node (ref "R15") (pin "1") (pinfunction "1_1") (pintype "passive"))
      (node (ref "U5") (pin "8") (pinfunction "VDD_8") (pintype "power_in"))
    )
    (net (code "59") (name "Net-(U6-BST)") (class "Default")
      (node (ref "C19") (pin "2") (pinfunction "2_2") (pintype "passive"))
      (node (ref "U6") (pin "7") (pinfunction "BST_7") (pintype "passive"))
    )
    (net (code "60") (name "Net-(U6-FB)") (class "Default")
      (node (ref "C20") (pin "1") (pinfunction "1_1") (pintype "passive"))
      (node (ref "R6") (pin "1") (pinfunction "1_1") (pintype "passive"))
      (node (ref "R8") (pin "2") (pinfunction "2_2") (pintype "passive"))
      (node (ref "U6") (pin "5") (pinfunction "FB_5") (pintype "passive"))
    )
    (net (code "61") (name "Net-(U6-SW)") (class "Default")
      (node (ref "C19") (pin "1") (pinfunction "1_1") (pintype "passive"))
      (node (ref "L2") (pin "1") (pinfunction "1_1") (pintype "passive"))
      (node (ref "U6") (pin "8") (pinfunction "SW_8") (pintype "passive"))
    )
    (net (code "62") (name "Net-(U6-VCC)") (class "Default")
      (node (ref "C22") (pin "2") (pinfunction "2_2") (pintype "passive"))
      (node (ref "U6") (pin "4") (pinfunction "VCC_4") (pintype "passive"))
    )
    (net (code "63") (name "Net-(U8-VC)") (class "Default")
      (node (ref "C12") (pin "1") (pinfunction "1_1") (pintype "passive"))
      (node (ref "U8") (pin "3") (pinfunction "VC_3") (pintype "passive"))
    )
    (net (code "64") (name "VDD_ENV") (class "Default")
      (node (ref "C11") (pin "1") (pinfunction "1_1") (pintype "passive"))
      (node (ref "C13") (pin "1") (pinfunction "1_1") (pintype "passive"))
      (node (ref "C14") (pin "1") (pinfunction "1_1") (pintype "passive"))
      (node (ref "C5") (pin "1") (pinfunction "1_1") (pintype "passive"))
      (node (ref "C7") (pin "2") (pinfunction "2_2") (pintype "passive"))
      (node (ref "U1") (pin "49") (pinfunction "QSPID2/GPIO49/P0.22_49") (pintype "passive"))
      (node (ref "U2") (pin "12") (pinfunction "CSB_12") (pintype "passive"))
      (node (ref "U2") (pin "5") (pinfunction "VDDIO_5") (pintype "passive"))
      (node (ref "U2") (pin "8") (pinfunction "VDD_8") (pintype "passive"))
      (node (ref "U7") (pin "A1") (pinfunction "PS_A1") (pintype "passive"))
      (node (ref "U7") (pin "B2") (pinfunction "VDDIO_B2") (pintype "passive"))
      (node (ref "U7") (pin "E5") (pinfunction "VDD_E5") (pintype "passive"))
      (node (ref "U8") (pin "4") (pinfunction "VDD_4") (pintype "passive"))
      (node (ref "U9") (pin "1") (pinfunction "VCCIO_1") (pintype "passive"))
      (node (ref "U9") (pin "10") (pinfunction "VCC_10") (pintype "passive"))
      (node (ref "U9") (pin "6") (pinfunction "CS_6") (pintype "passive"))
    )
    (net (code "65") (name "VIN") (class "Default")
      (node (ref "C23") (pin "2") (pinfunction "2_2") (pintype "passive"))
      (node (ref "C24") (pin "1") (pinfunction "1_1") (pintype "passive"))
      (node (ref "C25") (pin "2") (pinfunction "2_2") (pintype "passive"))
      (node (ref "C4") (pin "2") (pinfunction "2_2") (pintype "passive"))
      (node (ref "D2") (pin "C") (pinfunction "C_C") (pintype "passive"))
      (node (ref "JP2") (pin "15") (pinfunction "VIN_15") (pintype "passive"))
      (node (ref "U6") (pin "2") (pinfunction "IN_2") (pintype "passive"))
      (node (ref "U6") (pin "3") (pinfunction "EN_3") (pintype "passive"))
    )
    (net (code "66") (name "VUSB") (class "Default")
      (node (ref "C6") (pin "1") (pinfunction "1_1") (pintype "passive"))
      (node (ref "D1") (pin "4") (pinfunction "4_4") (pintype "passive"))
      (node (ref "D2") (pin "A") (pinfunction "A_A") (pintype "passive"))
      (node (ref "J1") (pin "1") (pinfunction "1_1") (pintype "passive"))
      (node (ref "L1") (pin "1") (pinfunction "1_1") (pintype "passive"))
      (node (ref "SJ1") (pin "1") (pinfunction "1_1") (pintype "passive"))
      (node (ref "SJ5") (pin "1") (pinfunction "1_1") (pintype "passive"))
    )
    (net (code "67") (name "unconnected-(Fiducial_1-Pad1)") (class "Default")
      (node (ref "Fiducial_1") (pin "1") (pinfunction "1_1") (pintype "passive+no_connect"))
    )
    (net (code "68") (name "unconnected-(Fiducial_2-Pad1)") (class "Default")
      (node (ref "Fiducial_2") (pin "1") (pinfunction "1_1") (pintype "passive+no_connect"))
    )
    (net (code "69") (name "unconnected-(J1-Pad4)") (class "Default")
      (node (ref "J1") (pin "4") (pinfunction "4_4") (pintype "passive+no_connect"))
    )
    (net (code "70") (name "unconnected-(U1-ANT-Pad13)") (class "Default")
      (node (ref "U1") (pin "13") (pinfunction "ANT_13") (pintype "passive+no_connect"))
    )
    (net (code "71") (name "unconnected-(U1-TRACECLK{slash}GPIO45{slash}P0.07-Pad45)") (class "Default")
      (node (ref "U1") (pin "45") (pinfunction "TRACECLK/GPIO45/P0.07_45") (pintype "passive+no_connect"))
    )
    (net (code "72") (name "unconnected-(U2-ASCx-Pad3)") (class "Default")
      (node (ref "U2") (pin "3") (pinfunction "ASCx_3") (pintype "passive+no_connect"))
    )
    (net (code "73") (name "unconnected-(U2-ASDx-Pad2)") (class "Default")
      (node (ref "U2") (pin "2") (pinfunction "ASDx_2") (pintype "passive+no_connect"))
    )
    (net (code "74") (name "unconnected-(U2-OCSB-Pad10)") (class "Default")
      (node (ref "U2") (pin "10") (pinfunction "OCSB_10") (pintype "passive+no_connect"))
    )
    (net (code "75") (name "unconnected-(U2-OSDO-Pad11)") (class "Default")
      (node (ref "U2") (pin "11") (pinfunction "OSDO_11") (pintype "passive+no_connect"))
    )
    (net (code "76") (name "unconnected-(U4-NC-Pad1)") (class "Default")
      (node (ref "U4") (pin "1") (pinfunction "NC_1") (pintype "passive+no_connect"))
    )
    (net (code "77") (name "unconnected-(U4-NC-Pad2)") (class "Default")
      (node (ref "U4") (pin "2") (pinfunction "NC_2") (pintype "passive+no_connect"))
    )
    (net (code "78") (name "unconnected-(U4-NC-Pad3)") (class "Default")
      (node (ref "U4") (pin "3") (pinfunction "NC_3") (pintype "passive+no_connect"))
    )
    (net (code "79") (name "unconnected-(U4-NC-Pad7)") (class "Default")
      (node (ref "U4") (pin "7") (pinfunction "NC_7") (pintype "passive+no_connect"))
    )
    (net (code "80") (name "unconnected-(U4-NC-Pad9)") (class "Default")
      (node (ref "U4") (pin "9") (pinfunction "NC_9") (pintype "passive+no_connect"))
    )
    (net (code "81") (name "unconnected-(U6-PG-Pad6)") (class "Default")
      (node (ref "U6") (pin "6") (pinfunction "PG_6") (pintype "passive+no_connect"))
    )
    (net (code "82") (name "unconnected-(U7-DRDY-PadD4)") (class "Default")
      (node (ref "U7") (pin "D4") (pinfunction "DRDY_D4") (pintype "passive+no_connect"))
    )
    (net (code "83") (name "unconnected-(U7-INT-PadD2)") (class "Default")
      (node (ref "U7") (pin "D2") (pinfunction "INT_D2") (pintype "passive+no_connect"))
    )
    (net (code "84") (name "unconnected-(U8-NC-Pad5)") (class "Default")
      (node (ref "U8") (pin "5") (pinfunction "NC_5") (pintype "passive+no_connect"))
    )
  )
)
